# AFE.net
KiCad netlist of a schematic drawn in Altium Designer
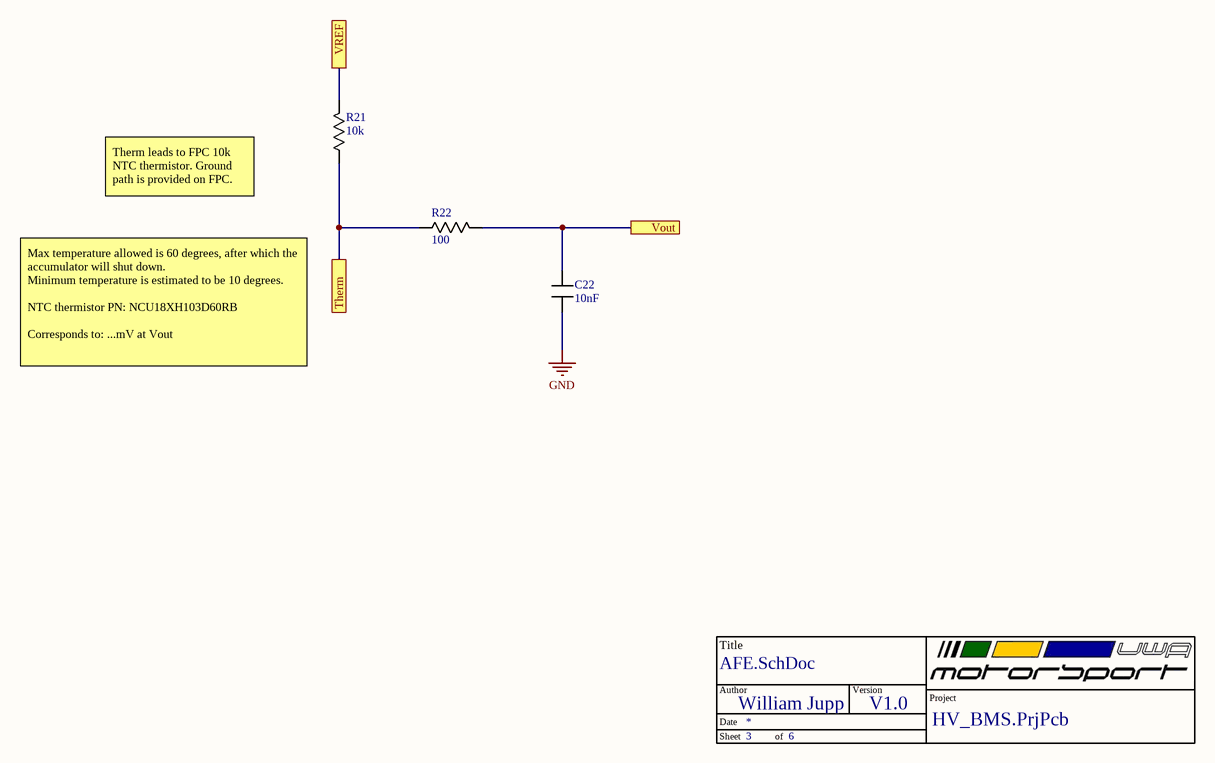
[diagram p0: AFE.SchDoc]

(export (version "E")
  (design (tool "Eeschema 10.0.6"))
  (components
    (comp (ref "*") (value "TitleBlock") (libsource (lib "HV_BMS_SCH_LIB") (part "TitleBlock")))
    (comp (ref "C22")
      (value "10nF")
      (footprint "C_0603")
      (description "Capacitor")
      (fields (field (name "Comment") "C"))
      (libsource (lib "Passives") (part "Capacitor"))
    )
    (comp (ref "R21")
      (value "10k")
      (footprint "R-0603")
      (description "Res Thin Film 0603 10K Ohm 0.1% 0.1W(1/10W) ±25ppm/C Pad SMD T/R")
      (fields
        (field (name "MANUFACTURER") "Bourns")
        (field (name "MANUFACTURER PART NUMBER") "CRT0603-BY-1002EST")
      )
      (libsource (lib "Passives") (part "Resistor"))
    )
    (comp (ref "R22")
      (value "100")
      (footprint "R-0603")
      (description "Resistor")
      (libsource (lib "Passives") (part "Resistor"))
    )
  )
  (nets
    (net (code "1") (name "/Therm") (class "Default")
      (node (ref "R21") (pin "1") (pinfunction "1_1") (pintype "passive"))
      (node (ref "R22") (pin "1") (pinfunction "1_1") (pintype "passive"))
    )
    (net (code "2") (name "/VREF") (class "Default")
      (node (ref "R21") (pin "2") (pinfunction "2_2") (pintype "passive"))
    )
    (net (code "3") (name "/Vout") (class "Default")
      (node (ref "C22") (pin "2") (pinfunction "2_2") (pintype "passive"))
      (node (ref "R22") (pin "2") (pinfunction "2_2") (pintype "passive"))
    )
    (net (code "4") (name "GND") (class "Default")
      (node (ref "C22") (pin "1") (pinfunction "1_1") (pintype "passive"))
    )
  )
)
